# TDA7492.net
KiCad netlist of a schematic drawn in EAGLE
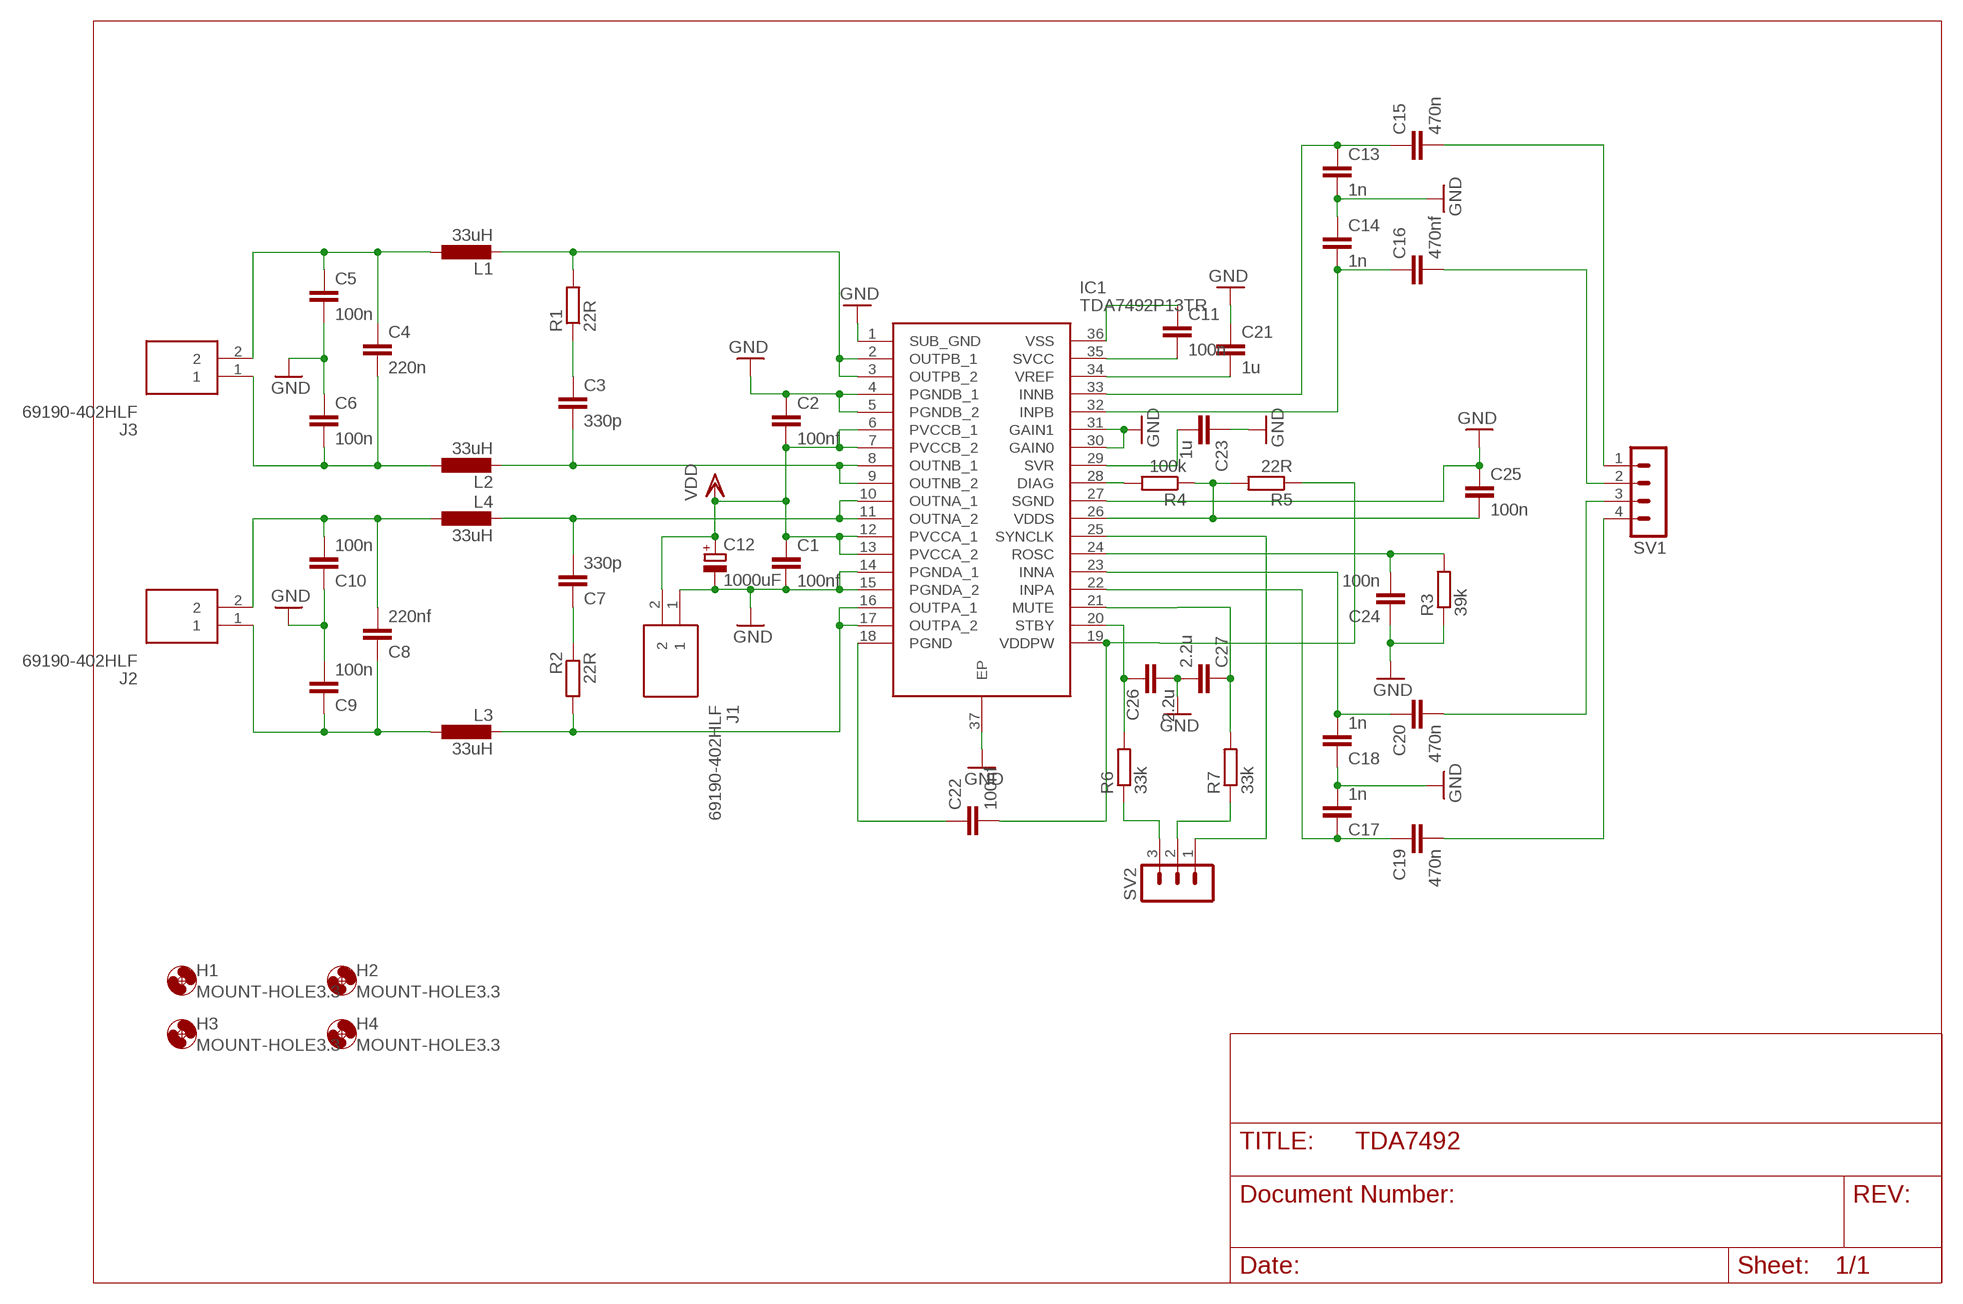
[diagram p0: schematic, sheet 1]

(export (version "E")
  (design (tool "Eeschema 10.0.6"))
  (components
    (comp (ref "C1")
      (value "100nf")
      (footprint "eagle-import:C0805")
      (libsource (lib "eagle-import") (part "C-EUC0805"))
    )
    (comp (ref "C2")
      (value "100nf")
      (footprint "eagle-import:C0805")
      (libsource (lib "eagle-import") (part "C-EUC0805"))
    )
    (comp (ref "C3")
      (value "330p")
      (footprint "eagle-import:C0805")
      (libsource (lib "eagle-import") (part "C-EUC0805"))
    )
    (comp (ref "C4")
      (value "220n")
      (footprint "eagle-import:C0805")
      (libsource (lib "eagle-import") (part "C-EUC0805"))
    )
    (comp (ref "C5")
      (value "100n")
      (footprint "eagle-import:C0805")
      (libsource (lib "eagle-import") (part "C-EUC0805"))
    )
    (comp (ref "C6")
      (value "100n")
      (footprint "eagle-import:C0805")
      (libsource (lib "eagle-import") (part "C-EUC0805"))
    )
    (comp (ref "C7")
      (value "330p")
      (footprint "eagle-import:C0805")
      (libsource (lib "eagle-import") (part "C-EUC0805"))
    )
    (comp (ref "C8")
      (value "220nf")
      (footprint "eagle-import:C0805")
      (libsource (lib "eagle-import") (part "C-EUC0805"))
    )
    (comp (ref "C9")
      (value "100n")
      (footprint "eagle-import:C0805")
      (libsource (lib "eagle-import") (part "C-EUC0805"))
    )
    (comp (ref "C10")
      (value "100n")
      (footprint "eagle-import:C0805")
      (libsource (lib "eagle-import") (part "C-EUC0805"))
    )
    (comp (ref "C11")
      (value "100n")
      (footprint "eagle-import:C0805")
      (libsource (lib "eagle-import") (part "C-EUC0805"))
    )
    (comp (ref "C12")
      (value "1000uF")
      (footprint "eagle-import:E7,5-16")
      (libsource (lib "eagle-import") (part "CPOL-EUE7.5-16"))
    )
    (comp (ref "C13")
      (value "1n")
      (footprint "eagle-import:C0805")
      (libsource (lib "eagle-import") (part "C-EUC0805"))
    )
    (comp (ref "C14")
      (value "1n")
      (footprint "eagle-import:C0805")
      (libsource (lib "eagle-import") (part "C-EUC0805"))
    )
    (comp (ref "C15")
      (value "470n")
      (footprint "eagle-import:C0805")
      (libsource (lib "eagle-import") (part "C-EUC0805"))
    )
    (comp (ref "C16")
      (value "470nf")
      (footprint "eagle-import:C0805")
      (libsource (lib "eagle-import") (part "C-EUC0805"))
    )
    (comp (ref "C17")
      (value "1n")
      (footprint "eagle-import:C0805")
      (libsource (lib "eagle-import") (part "C-EUC0805"))
    )
    (comp (ref "C18")
      (value "1n")
      (footprint "eagle-import:C0805")
      (libsource (lib "eagle-import") (part "C-EUC0805"))
    )
    (comp (ref "C19")
      (value "470n")
      (footprint "eagle-import:C0805")
      (libsource (lib "eagle-import") (part "C-EUC0805"))
    )
    (comp (ref "C20")
      (value "470n")
      (footprint "eagle-import:C0805")
      (libsource (lib "eagle-import") (part "C-EUC0805"))
    )
    (comp (ref "C21")
      (value "1u")
      (footprint "eagle-import:C0805")
      (libsource (lib "eagle-import") (part "C-EUC0805"))
    )
    (comp (ref "C22")
      (value "100nf")
      (footprint "eagle-import:C0805")
      (libsource (lib "eagle-import") (part "C-EUC0805"))
    )
    (comp (ref "C23")
      (value "1u")
      (footprint "eagle-import:C0805")
      (libsource (lib "eagle-import") (part "C-EUC0805"))
    )
    (comp (ref "C24")
      (value "100n")
      (footprint "eagle-import:C0805")
      (libsource (lib "eagle-import") (part "C-EUC0805"))
    )
    (comp (ref "C25")
      (value "100n")
      (footprint "eagle-import:C0805")
      (libsource (lib "eagle-import") (part "C-EUC0805"))
    )
    (comp (ref "C26")
      (value "2.2u")
      (footprint "eagle-import:C0805")
      (libsource (lib "eagle-import") (part "C-EUC0805"))
    )
    (comp (ref "C27")
      (value "2.2u")
      (footprint "eagle-import:C0805")
      (libsource (lib "eagle-import") (part "C-EUC0805"))
    )
    (comp (ref "H1")
      (value "MOUNT-HOLE3.3")
      (footprint "eagle-import:3,3")
      (libsource (lib "eagle-import") (part "MOUNT-HOLE3.3"))
    )
    (comp (ref "H2")
      (value "MOUNT-HOLE3.3")
      (footprint "eagle-import:3,3")
      (libsource (lib "eagle-import") (part "MOUNT-HOLE3.3"))
    )
    (comp (ref "H3")
      (value "MOUNT-HOLE3.3")
      (footprint "eagle-import:3,3")
      (libsource (lib "eagle-import") (part "MOUNT-HOLE3.3"))
    )
    (comp (ref "H4")
      (value "MOUNT-HOLE3.3")
      (footprint "eagle-import:3,3")
      (libsource (lib "eagle-import") (part "MOUNT-HOLE3.3"))
    )
    (comp (ref "IC1")
      (value "TDA7492P13TR")
      (footprint "eagle-import:SOP50P1030X245-37N")
      (fields (field (name "MOUSER2_PART_NUMBER") "511-TDA7492P13TR"))
      (libsource (lib "eagle-import") (part "TDA7492P13TR"))
    )
    (comp (ref "J1")
      (value "69190-402HLF")
      (footprint "eagle-import:HDRV2W90P0X254_1X2_508X241X858")
      (fields (field (name "RS_PART_NUMBER") "8632731"))
      (libsource (lib "eagle-import") (part "69190-402HLF"))
    )
    (comp (ref "J2")
      (value "69190-402HLF")
      (footprint "eagle-import:HDRV2W90P0X254_1X2_508X241X858")
      (fields (field (name "RS_PART_NUMBER") "8632731"))
      (libsource (lib "eagle-import") (part "69190-402HLF"))
    )
    (comp (ref "J3")
      (value "69190-402HLF")
      (footprint "eagle-import:HDRV2W90P0X254_1X2_508X241X858")
      (fields (field (name "RS_PART_NUMBER") "8632731"))
      (libsource (lib "eagle-import") (part "69190-402HLF"))
    )
    (comp (ref "L1")
      (value "33uH")
      (footprint "eagle-import:POWER-CHOKE_WE-TPC")
      (libsource (lib "eagle-import") (part "L-EUWE-TPC"))
    )
    (comp (ref "L2")
      (value "33uH")
      (footprint "eagle-import:POWER-CHOKE_WE-TPC")
      (libsource (lib "eagle-import") (part "L-EUWE-TPC"))
    )
    (comp (ref "L3")
      (value "33uH")
      (footprint "eagle-import:POWER-CHOKE_WE-TPC")
      (libsource (lib "eagle-import") (part "L-EUWE-TPC"))
    )
    (comp (ref "L4")
      (value "33uH")
      (footprint "eagle-import:POWER-CHOKE_WE-TPC")
      (libsource (lib "eagle-import") (part "L-EUWE-TPC"))
    )
    (comp (ref "R1")
      (value "22R")
      (footprint "eagle-import:R0805")
      (libsource (lib "eagle-import") (part "R-EU_R0805"))
    )
    (comp (ref "R2")
      (value "22R")
      (footprint "eagle-import:R0805")
      (libsource (lib "eagle-import") (part "R-EU_R0805"))
    )
    (comp (ref "R3")
      (value "39k")
      (footprint "eagle-import:R0805")
      (libsource (lib "eagle-import") (part "R-EU_R0805"))
    )
    (comp (ref "R4")
      (value "100k")
      (footprint "eagle-import:R0805")
      (libsource (lib "eagle-import") (part "R-EU_R0805"))
    )
    (comp (ref "R5")
      (value "22R")
      (footprint "eagle-import:R0805")
      (libsource (lib "eagle-import") (part "R-EU_R0805"))
    )
    (comp (ref "R6")
      (value "33k")
      (footprint "eagle-import:R0805")
      (libsource (lib "eagle-import") (part "R-EU_R0805"))
    )
    (comp (ref "R7")
      (value "33k")
      (footprint "eagle-import:R0805")
      (libsource (lib "eagle-import") (part "R-EU_R0805"))
    )
    (comp (ref "SV1")
      (value "MA04-1")
      (footprint "eagle-import:MA04-1")
      (libsource (lib "eagle-import") (part "MA04-1"))
    )
    (comp (ref "SV2")
      (value "MA03-1")
      (footprint "eagle-import:MA03-1")
      (libsource (lib "eagle-import") (part "MA03-1"))
    )
  )
  (nets
    (net (code "1") (name "GND") (class "Default")
      (node (ref "C1") (pin "2") (pinfunction "2_2") (pintype "passive"))
      (node (ref "C10") (pin "1") (pinfunction "1_1") (pintype "passive"))
      (node (ref "C12") (pin "-") (pinfunction "-_-") (pintype "passive"))
      (node (ref "C13") (pin "2") (pinfunction "2_2") (pintype "passive"))
      (node (ref "C14") (pin "1") (pinfunction "1_1") (pintype "passive"))
      (node (ref "C17") (pin "2") (pinfunction "2_2") (pintype "passive"))
      (node (ref "C18") (pin "1") (pinfunction "1_1") (pintype "passive"))
      (node (ref "C2") (pin "1") (pinfunction "1_1") (pintype "passive"))
      (node (ref "C21") (pin "1") (pinfunction "1_1") (pintype "passive"))
      (node (ref "C23") (pin "1") (pinfunction "1_1") (pintype "passive"))
      (node (ref "C24") (pin "1") (pinfunction "1_1") (pintype "passive"))
      (node (ref "C25") (pin "1") (pinfunction "1_1") (pintype "passive"))
      (node (ref "C26") (pin "2") (pinfunction "2_2") (pintype "passive"))
      (node (ref "C27") (pin "2") (pinfunction "2_2") (pintype "passive"))
      (node (ref "C5") (pin "2") (pinfunction "2_2") (pintype "passive"))
      (node (ref "C6") (pin "1") (pinfunction "1_1") (pintype "passive"))
      (node (ref "C9") (pin "2") (pinfunction "2_2") (pintype "passive"))
      (node (ref "IC1") (pin "1") (pinfunction "SUB_GND_1") (pintype "bidirectional"))
      (node (ref "IC1") (pin "14") (pinfunction "PGNDA_1_14") (pintype "bidirectional"))
      (node (ref "IC1") (pin "15") (pinfunction "PGNDA_2_15") (pintype "bidirectional"))
      (node (ref "IC1") (pin "27") (pinfunction "SGND_27") (pintype "bidirectional"))
      (node (ref "IC1") (pin "30") (pinfunction "GAIN0_30") (pintype "bidirectional"))
      (node (ref "IC1") (pin "31") (pinfunction "GAIN1_31") (pintype "bidirectional"))
      (node (ref "IC1") (pin "37") (pinfunction "EP_37") (pintype "bidirectional"))
      (node (ref "IC1") (pin "4") (pinfunction "PGNDB_1_4") (pintype "bidirectional"))
      (node (ref "IC1") (pin "5") (pinfunction "PGNDB_2_5") (pintype "bidirectional"))
      (node (ref "J1") (pin "1") (pinfunction "1_1") (pintype "bidirectional"))
      (node (ref "R3") (pin "1") (pinfunction "1_1") (pintype "passive"))
    )
    (net (code "2") (name "Net-(C3-Pad1)") (class "Default")
      (node (ref "C3") (pin "1") (pinfunction "1_1") (pintype "passive"))
      (node (ref "R1") (pin "1") (pinfunction "1_1") (pintype "passive"))
    )
    (net (code "3") (name "Net-(C4-Pad1)") (class "Default")
      (node (ref "C4") (pin "1") (pinfunction "1_1") (pintype "passive"))
      (node (ref "C5") (pin "1") (pinfunction "1_1") (pintype "passive"))
      (node (ref "J3") (pin "2") (pinfunction "2_2") (pintype "bidirectional"))
      (node (ref "L1") (pin "1") (pinfunction "1_1") (pintype "passive"))
    )
    (net (code "4") (name "Net-(C4-Pad2)") (class "Default")
      (node (ref "C4") (pin "2") (pinfunction "2_2") (pintype "passive"))
      (node (ref "C6") (pin "2") (pinfunction "2_2") (pintype "passive"))
      (node (ref "J3") (pin "1") (pinfunction "1_1") (pintype "bidirectional"))
      (node (ref "L2") (pin "1") (pinfunction "1_1") (pintype "passive"))
    )
    (net (code "5") (name "Net-(C7-Pad1)") (class "Default")
      (node (ref "C7") (pin "1") (pinfunction "1_1") (pintype "passive"))
      (node (ref "R2") (pin "1") (pinfunction "1_1") (pintype "passive"))
    )
    (net (code "6") (name "Net-(C8-Pad1)") (class "Default")
      (node (ref "C8") (pin "1") (pinfunction "1_1") (pintype "passive"))
      (node (ref "C9") (pin "1") (pinfunction "1_1") (pintype "passive"))
      (node (ref "J2") (pin "1") (pinfunction "1_1") (pintype "bidirectional"))
      (node (ref "L3") (pin "1") (pinfunction "1_1") (pintype "passive"))
    )
    (net (code "7") (name "Net-(C10-Pad2)") (class "Default")
      (node (ref "C10") (pin "2") (pinfunction "2_2") (pintype "passive"))
      (node (ref "C8") (pin "2") (pinfunction "2_2") (pintype "passive"))
      (node (ref "J2") (pin "2") (pinfunction "2_2") (pintype "bidirectional"))
      (node (ref "L4") (pin "1") (pinfunction "1_1") (pintype "passive"))
    )
    (net (code "8") (name "Net-(C15-Pad2)") (class "Default")
      (node (ref "C15") (pin "2") (pinfunction "2_2") (pintype "passive"))
      (node (ref "SV1") (pin "1") (pinfunction "1_1") (pintype "passive"))
    )
    (net (code "9") (name "Net-(C16-Pad2)") (class "Default")
      (node (ref "C16") (pin "2") (pinfunction "2_2") (pintype "passive"))
      (node (ref "SV1") (pin "2") (pinfunction "2_2") (pintype "passive"))
    )
    (net (code "10") (name "Net-(C19-Pad2)") (class "Default")
      (node (ref "C19") (pin "2") (pinfunction "2_2") (pintype "passive"))
      (node (ref "SV1") (pin "4") (pinfunction "4_4") (pintype "passive"))
    )
    (net (code "11") (name "Net-(C20-Pad2)") (class "Default")
      (node (ref "C20") (pin "2") (pinfunction "2_2") (pintype "passive"))
      (node (ref "SV1") (pin "3") (pinfunction "3_3") (pintype "passive"))
    )
    (net (code "12") (name "Net-(IC1-DIAG)") (class "Default")
      (node (ref "IC1") (pin "28") (pinfunction "DIAG_28") (pintype "bidirectional"))
      (node (ref "R4") (pin "2") (pinfunction "2_2") (pintype "passive"))
    )
    (net (code "13") (name "Net-(IC1-INNA)") (class "Default")
      (node (ref "C18") (pin "2") (pinfunction "2_2") (pintype "passive"))
      (node (ref "C20") (pin "1") (pinfunction "1_1") (pintype "passive"))
      (node (ref "IC1") (pin "23") (pinfunction "INNA_23") (pintype "bidirectional"))
    )
    (net (code "14") (name "Net-(IC1-INNB)") (class "Default")
      (node (ref "C13") (pin "1") (pinfunction "1_1") (pintype "passive"))
      (node (ref "C15") (pin "1") (pinfunction "1_1") (pintype "passive"))
      (node (ref "IC1") (pin "33") (pinfunction "INNB_33") (pintype "bidirectional"))
    )
    (net (code "15") (name "Net-(IC1-INPA)") (class "Default")
      (node (ref "C17") (pin "1") (pinfunction "1_1") (pintype "passive"))
      (node (ref "C19") (pin "1") (pinfunction "1_1") (pintype "passive"))
      (node (ref "IC1") (pin "22") (pinfunction "INPA_22") (pintype "bidirectional"))
    )
    (net (code "16") (name "Net-(IC1-INPB)") (class "Default")
      (node (ref "C14") (pin "2") (pinfunction "2_2") (pintype "passive"))
      (node (ref "C16") (pin "1") (pinfunction "1_1") (pintype "passive"))
      (node (ref "IC1") (pin "32") (pinfunction "INPB_32") (pintype "bidirectional"))
    )
    (net (code "17") (name "Net-(IC1-MUTE)") (class "Default")
      (node (ref "C27") (pin "1") (pinfunction "1_1") (pintype "passive"))
      (node (ref "IC1") (pin "21") (pinfunction "MUTE_21") (pintype "bidirectional"))
      (node (ref "R7") (pin "2") (pinfunction "2_2") (pintype "passive"))
    )
    (net (code "18") (name "Net-(IC1-OUTNA_1)") (class "Default")
      (node (ref "C7") (pin "2") (pinfunction "2_2") (pintype "passive"))
      (node (ref "IC1") (pin "10") (pinfunction "OUTNA_1_10") (pintype "bidirectional"))
      (node (ref "IC1") (pin "11") (pinfunction "OUTNA_2_11") (pintype "bidirectional"))
      (node (ref "L4") (pin "2") (pinfunction "2_2") (pintype "passive"))
    )
    (net (code "19") (name "Net-(IC1-OUTNB_1)") (class "Default")
      (node (ref "C3") (pin "2") (pinfunction "2_2") (pintype "passive"))
      (node (ref "IC1") (pin "8") (pinfunction "OUTNB_1_8") (pintype "bidirectional"))
      (node (ref "IC1") (pin "9") (pinfunction "OUTNB_2_9") (pintype "bidirectional"))
      (node (ref "L2") (pin "2") (pinfunction "2_2") (pintype "passive"))
    )
    (net (code "20") (name "Net-(IC1-OUTPA_1)") (class "Default")
      (node (ref "IC1") (pin "16") (pinfunction "OUTPA_1_16") (pintype "bidirectional"))
      (node (ref "IC1") (pin "17") (pinfunction "OUTPA_2_17") (pintype "bidirectional"))
      (node (ref "L3") (pin "2") (pinfunction "2_2") (pintype "passive"))
      (node (ref "R2") (pin "2") (pinfunction "2_2") (pintype "passive"))
    )
    (net (code "21") (name "Net-(IC1-OUTPB_1)") (class "Default")
      (node (ref "IC1") (pin "2") (pinfunction "OUTPB_1_2") (pintype "bidirectional"))
      (node (ref "IC1") (pin "3") (pinfunction "OUTPB_2_3") (pintype "bidirectional"))
      (node (ref "L1") (pin "2") (pinfunction "2_2") (pintype "passive"))
      (node (ref "R1") (pin "2") (pinfunction "2_2") (pintype "passive"))
    )
    (net (code "22") (name "Net-(IC1-PGND)") (class "Default")
      (node (ref "C22") (pin "1") (pinfunction "1_1") (pintype "passive"))
      (node (ref "IC1") (pin "18") (pinfunction "PGND_18") (pintype "bidirectional"))
    )
    (net (code "23") (name "Net-(IC1-ROSC)") (class "Default")
      (node (ref "C24") (pin "2") (pinfunction "2_2") (pintype "passive"))
      (node (ref "IC1") (pin "24") (pinfunction "ROSC_24") (pintype "bidirectional"))
      (node (ref "R3") (pin "2") (pinfunction "2_2") (pintype "passive"))
    )
    (net (code "24") (name "Net-(IC1-STBY)") (class "Default")
      (node (ref "C26") (pin "1") (pinfunction "1_1") (pintype "passive"))
      (node (ref "IC1") (pin "20") (pinfunction "STBY_20") (pintype "bidirectional"))
      (node (ref "R6") (pin "2") (pinfunction "2_2") (pintype "passive"))
    )
    (net (code "25") (name "Net-(IC1-SVCC)") (class "Default")
      (node (ref "C11") (pin "2") (pinfunction "2_2") (pintype "passive"))
      (node (ref "IC1") (pin "35") (pinfunction "SVCC_35") (pintype "bidirectional"))
    )
    (net (code "26") (name "Net-(IC1-SVR)") (class "Default")
      (node (ref "C23") (pin "2") (pinfunction "2_2") (pintype "passive"))
      (node (ref "IC1") (pin "29") (pinfunction "SVR_29") (pintype "bidirectional"))
    )
    (net (code "27") (name "Net-(IC1-SYNCLK)") (class "Default")
      (node (ref "IC1") (pin "25") (pinfunction "SYNCLK_25") (pintype "bidirectional"))
      (node (ref "SV2") (pin "1") (pinfunction "1_1") (pintype "passive"))
    )
    (net (code "28") (name "Net-(IC1-VDDPW)") (class "Default")
      (node (ref "C22") (pin "2") (pinfunction "2_2") (pintype "passive"))
      (node (ref "IC1") (pin "19") (pinfunction "VDDPW_19") (pintype "bidirectional"))
      (node (ref "R5") (pin "1") (pinfunction "1_1") (pintype "passive"))
    )
    (net (code "29") (name "Net-(IC1-VDDS)") (class "Default")
      (node (ref "C25") (pin "2") (pinfunction "2_2") (pintype "passive"))
      (node (ref "IC1") (pin "26") (pinfunction "VDDS_26") (pintype "bidirectional"))
      (node (ref "R4") (pin "1") (pinfunction "1_1") (pintype "passive"))
      (node (ref "R5") (pin "2") (pinfunction "2_2") (pintype "passive"))
    )
    (net (code "30") (name "Net-(IC1-VREF)") (class "Default")
      (node (ref "C21") (pin "2") (pinfunction "2_2") (pintype "passive"))
      (node (ref "IC1") (pin "34") (pinfunction "VREF_34") (pintype "bidirectional"))
    )
    (net (code "31") (name "Net-(IC1-VSS)") (class "Default")
      (node (ref "C11") (pin "1") (pinfunction "1_1") (pintype "passive"))
      (node (ref "IC1") (pin "36") (pinfunction "VSS_36") (pintype "bidirectional"))
    )
    (net (code "32") (name "Net-(R6-Pad1)") (class "Default")
      (node (ref "R6") (pin "1") (pinfunction "1_1") (pintype "passive"))
      (node (ref "SV2") (pin "3") (pinfunction "3_3") (pintype "passive"))
    )
    (net (code "33") (name "Net-(R7-Pad1)") (class "Default")
      (node (ref "R7") (pin "1") (pinfunction "1_1") (pintype "passive"))
      (node (ref "SV2") (pin "2") (pinfunction "2_2") (pintype "passive"))
    )
    (net (code "34") (name "VDD") (class "Default")
      (node (ref "C1") (pin "1") (pinfunction "1_1") (pintype "passive"))
      (node (ref "C12") (pin "+") (pinfunction "+_+") (pintype "passive"))
      (node (ref "C2") (pin "2") (pinfunction "2_2") (pintype "passive"))
      (node (ref "IC1") (pin "12") (pinfunction "PVCCA_1_12") (pintype "bidirectional"))
      (node (ref "IC1") (pin "13") (pinfunction "PVCCA_2_13") (pintype "bidirectional"))
      (node (ref "IC1") (pin "6") (pinfunction "PVCCB_1_6") (pintype "bidirectional"))
      (node (ref "IC1") (pin "7") (pinfunction "PVCCB_2_7") (pintype "bidirectional"))
      (node (ref "J1") (pin "2") (pinfunction "2_2") (pintype "bidirectional"))
    )
  )
)
